# ADC_GPIO_Expander.net
KiCad netlist of a schematic drawn in Altium Designer
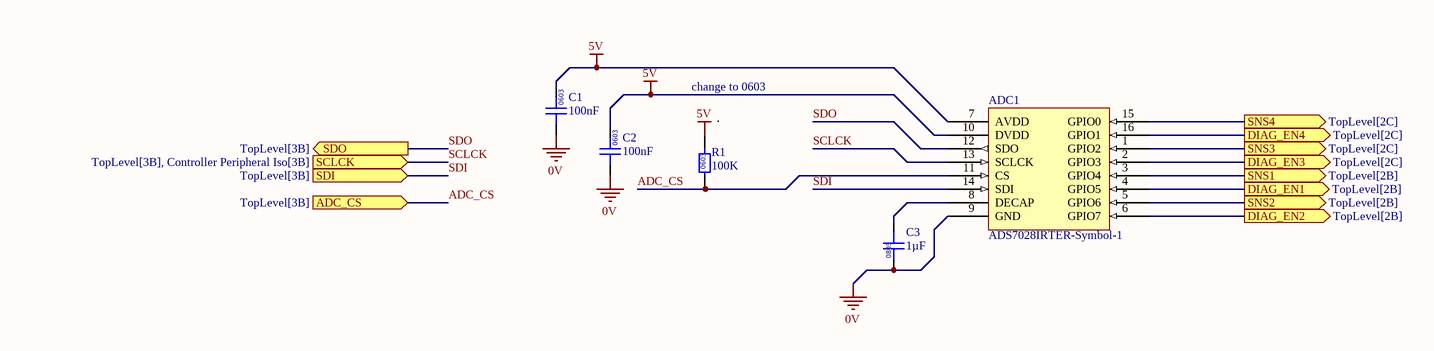
[diagram p0: ADC GPIO Expander.SchDoc]

(export (version "E")
  (design (tool "Eeschema 10.0.6"))
  (components
    (comp (ref "ADC1")
      (value "ADS7028IRTER-Symbol-1")
      (footprint "WFQN-16")
      (description "IC ADC 12BIT SAR 16WQFN")
      (fields (field (name "PART NUMBER") "ADS7028IRTER") (field (name "MANUFACTURER") "Texas Instruments"))
      (libsource (lib "ts_standard_library") (part "ADS7028IRTER"))
    )
    (comp (ref "C1")
      (value "100nF")
      (footprint "0603")
      (fields
        (field (name "PART NUMBER") "GCM188L81H104KA57D")
        (field (name "MANUFACTURER") "muRata")
        (field (name "TOLERANCE") "±10%")
      )
      (libsource (lib "ts_standard_library") (part "Capacitor 0603"))
    )
    (comp (ref "C2")
      (value "100nF")
      (footprint "0603")
      (fields
        (field (name "PART NUMBER") "GCM188L81H104KA57D")
        (field (name "MANUFACTURER") "muRata")
        (field (name "TOLERANCE") "±10%")
      )
      (libsource (lib "ts_standard_library") (part "Capacitor 0603"))
    )
    (comp (ref "C3")
      (value "1µF")
      (footprint "0805")
      (fields
        (field (name "PART NUMBER") "GCM21BR71H105KA03L")
        (field (name "MANUFACTURER") "muRata")
        (field (name "TOLERANCE") "±10%")
      )
      (libsource (lib "ts_standard_library") (part "Capacitor 0805"))
    )
    (comp (ref "R1")
      (value "100K")
      (footprint "0603")
      (fields
        (field (name "PART NUMBER") "RC0603FR-07100KL")
        (field (name "MANUFACTURER") "YAGEO")
        (field (name "TOLERANCE") "0.01")
      )
      (libsource (lib "ts_standard_library") (part "Resistor 0603"))
    )
  )
  (nets
    (net (code "1") (name "/ADC_CS") (class "Default")
      (node (ref "ADC1") (pin "11") (pinfunction "CS_11") (pintype "input"))
      (node (ref "R1") (pin "1") (pinfunction "1_1") (pintype "passive"))
    )
    (net (code "2") (name "/DIAG_EN1") (class "Default")
      (node (ref "ADC1") (pin "4") (pinfunction "GPIO5_4") (pintype "input"))
    )
    (net (code "3") (name "/DIAG_EN2") (class "Default")
      (node (ref "ADC1") (pin "6") (pinfunction "GPIO7_6") (pintype "input"))
    )
    (net (code "4") (name "/DIAG_EN3") (class "Default")
      (node (ref "ADC1") (pin "2") (pinfunction "GPIO3_2") (pintype "input"))
    )
    (net (code "5") (name "/DIAG_EN4") (class "Default")
      (node (ref "ADC1") (pin "16") (pinfunction "GPIO1_16") (pintype "input"))
    )
    (net (code "6") (name "/SCLCK") (class "Default")
      (node (ref "ADC1") (pin "13") (pinfunction "SCLCK_13") (pintype "input"))
    )
    (net (code "7") (name "/SDI") (class "Default")
      (node (ref "ADC1") (pin "14") (pinfunction "SDI_14") (pintype "input"))
    )
    (net (code "8") (name "/SDO") (class "Default")
      (node (ref "ADC1") (pin "12") (pinfunction "SDO_12") (pintype "output"))
    )
    (net (code "9") (name "/SNS1") (class "Default")
      (node (ref "ADC1") (pin "3") (pinfunction "GPIO4_3") (pintype "input"))
    )
    (net (code "10") (name "/SNS2") (class "Default")
      (node (ref "ADC1") (pin "5") (pinfunction "GPIO6_5") (pintype "input"))
    )
    (net (code "11") (name "/SNS3") (class "Default")
      (node (ref "ADC1") (pin "1") (pinfunction "GPIO2_1") (pintype "input"))
    )
    (net (code "12") (name "/SNS4") (class "Default")
      (node (ref "ADC1") (pin "15") (pinfunction "GPIO0_15") (pintype "input"))
    )
    (net (code "13") (name "0V") (class "Default")
      (node (ref "ADC1") (pin "9") (pinfunction "GND_9") (pintype "power_in"))
      (node (ref "C1") (pin "1") (pinfunction "1_1") (pintype "passive"))
      (node (ref "C2") (pin "1") (pinfunction "1_1") (pintype "passive"))
      (node (ref "C3") (pin "1") (pinfunction "1_1") (pintype "passive"))
    )
    (net (code "14") (name "5V") (class "Default")
      (node (ref "ADC1") (pin "10") (pinfunction "DVDD_10") (pintype "power_in"))
      (node (ref "ADC1") (pin "7") (pinfunction "AVDD_7") (pintype "power_in"))
      (node (ref "C1") (pin "2") (pinfunction "2_2") (pintype "passive"))
      (node (ref "C2") (pin "2") (pinfunction "2_2") (pintype "passive"))
      (node (ref "R1") (pin "2") (pinfunction "2_2") (pintype "passive"))
    )
    (net (code "15") (name "Net-(ADC1-DECAP)") (class "Default")
      (node (ref "ADC1") (pin "8") (pinfunction "DECAP_8") (pintype "power_in"))
      (node (ref "C3") (pin "2") (pinfunction "2_2") (pintype "passive"))
    )
  )
)
